# LDConnector.net
KiCad netlist of a schematic drawn in EAGLE
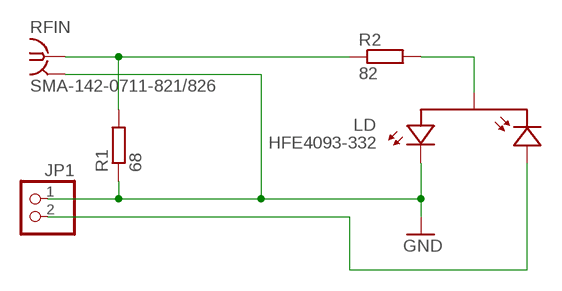
[diagram p0: schematic, sheet 1]

(export (version "E")
  (design (tool "Eeschema 10.0.6"))
  (components
    (comp (ref "JP1")
      (value "PINHD-1X2/90")
      (footprint "eagle-import:1X02_90")
      (libsource (lib "eagle-import") (part "PINHD-1X2/90"))
    )
    (comp (ref "LD")
      (value "HFE4093-332")
      (footprint "eagle-import:HFE4093-332-EDGE")
      (libsource (lib "eagle-import") (part "HFE4093-332"))
    )
    (comp (ref "R1")
      (value "68")
      (footprint "eagle-import:R0603")
      (libsource (lib "eagle-import") (part "R-EU_R0603"))
    )
    (comp (ref "R2")
      (value "82")
      (footprint "eagle-import:R0603")
      (libsource (lib "eagle-import") (part "R-EU_R0603"))
    )
    (comp (ref "RFIN")
      (value "SMA-142-0711-821/826")
      (footprint "eagle-import:J502-ND-142-0711-821_826")
      (fields (field (name "MF") "JOHNSON COMPONENTS") (field (name "MPN") "142-0711-821"))
      (libsource (lib "eagle-import") (part "SMA-142-0711-821/826"))
    )
  )
  (nets
    (net (code "1") (name "GND") (class "Default")
      (node (ref "JP1") (pin "1") (pinfunction "1_1") (pintype "passive"))
      (node (ref "LD") (pin "1-LD-CATHODE") (pinfunction "LDC_1-LD-CATHODE") (pintype "passive"))
      (node (ref "R1") (pin "1") (pinfunction "1_1") (pintype "passive"))
      (node (ref "RFIN") (pin "G@1") (pinfunction "2_G@1") (pintype "passive"))
      (node (ref "RFIN") (pin "G@2") (pinfunction "2_G@2") (pintype "passive"))
      (node (ref "RFIN") (pin "G@3") (pinfunction "2_G@3") (pintype "passive"))
      (node (ref "RFIN") (pin "G@4") (pinfunction "2_G@4") (pintype "passive"))
    )
    (net (code "2") (name "Net-(LD-LDA-PDC)") (class "Default")
      (node (ref "LD") (pin "2-PD-CATHODE-LD-ANODE") (pinfunction "LDA-PDC_2-PD-CATHODE-LD-ANODE") (pintype "passive"))
      (node (ref "R2") (pin "2") (pinfunction "2_2") (pintype "passive"))
    )
    (net (code "3") (name "Net-(LD-PDA)") (class "Default")
      (node (ref "JP1") (pin "2") (pinfunction "2_2") (pintype "passive"))
      (node (ref "LD") (pin "3-PD-ANODE") (pinfunction "PDA_3-PD-ANODE") (pintype "passive"))
    )
    (net (code "4") (name "Net-(R1-Pad2)") (class "Default")
      (node (ref "R1") (pin "2") (pinfunction "2_2") (pintype "passive"))
      (node (ref "R2") (pin "1") (pinfunction "1_1") (pintype "passive"))
      (node (ref "RFIN") (pin "1") (pinfunction "1_1") (pintype "passive"))
    )
  )
)
